# Automatic-Garden-Waterer.net
KiCad netlist of a schematic drawn in EAGLE
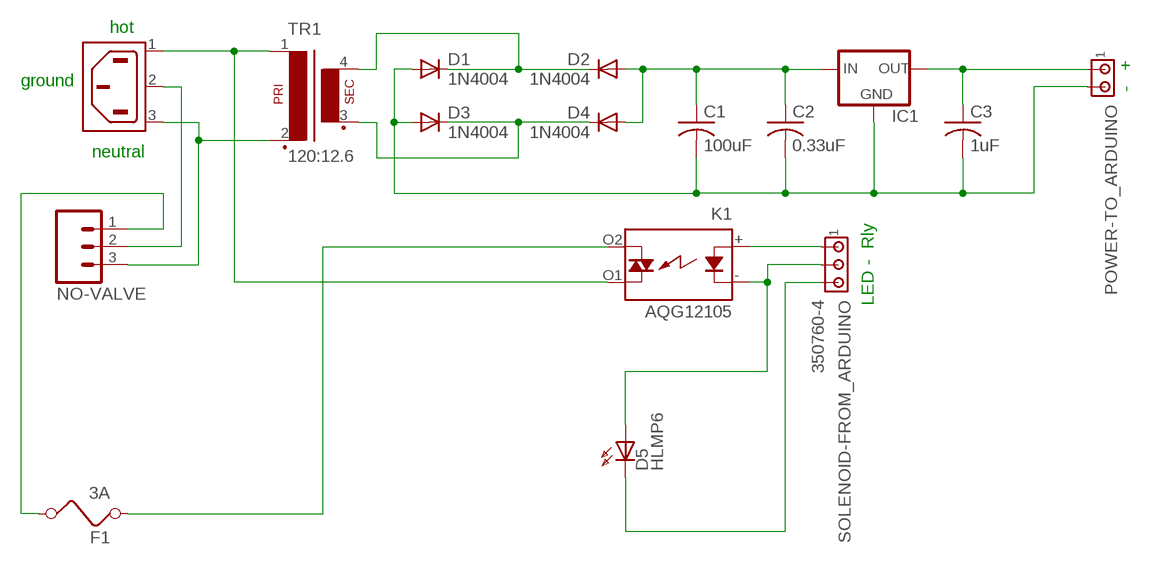
[diagram p0: schematic, sheet 1]

(export (version "E")
  (design (tool "Eeschema 10.0.6"))
  (components
    (comp (ref "C1")
      (value "100uF")
      (footprint "eagle-import:C075-032X103")
      (libsource (lib "eagle-import") (part "C-US075-032X103"))
    )
    (comp (ref "C2")
      (value "0.33uF")
      (footprint "eagle-import:C075-032X103")
      (libsource (lib "eagle-import") (part "C-US075-032X103"))
    )
    (comp (ref "C3")
      (value "1uF")
      (footprint "eagle-import:C075-032X103")
      (libsource (lib "eagle-import") (part "C-US075-032X103"))
    )
    (comp (ref "D1")
      (value "1N4004")
      (footprint "eagle-import:DO41-10")
      (libsource (lib "eagle-import") (part "1N4004"))
    )
    (comp (ref "D2")
      (value "1N4004")
      (footprint "eagle-import:DO41-10")
      (libsource (lib "eagle-import") (part "1N4004"))
    )
    (comp (ref "D3")
      (value "1N4004")
      (footprint "eagle-import:DO41-10")
      (libsource (lib "eagle-import") (part "1N4004"))
    )
    (comp (ref "D4")
      (value "1N4004")
      (footprint "eagle-import:DO41-10")
      (libsource (lib "eagle-import") (part "1N4004"))
    )
    (comp (ref "D5")
      (value "HLMP6")
      (footprint "eagle-import:HLMP6")
      (fields (field (name "MF") "AGILENT TECHNOLOGIES") (field (name "MPN") "HLMP-6500"))
      (libsource (lib "eagle-import") (part "HLMP6"))
    )
    (comp (ref "F1")
      (value "3A")
      (footprint "eagle-import:FUSE")
      (libsource (lib "eagle-import") (part "FUSE"))
    )
    (comp (ref "IC1")
      (value "V_REG_78XXSIDE")
      (footprint "eagle-import:78XXL")
      (libsource (lib "eagle-import") (part "V_REG_78XXSIDE"))
    )
    (comp (ref "K1")
      (value "AQG12105")
      (footprint "eagle-import:AQG")
      (fields (field (name "MF") "AROMAT/ MATSUSHITA"))
      (libsource (lib "eagle-import") (part "AQG12105"))
    )
    (comp (ref "NO-VALVE")
      (value "M03PTH")
      (footprint "eagle-import:1X03")
      (libsource (lib "eagle-import") (part "M03PTH"))
    )
    (comp (ref "POWER-TO_ARDUINO")
      (value "MTA02-100")
      (footprint "eagle-import:10X02MTA")
      (libsource (lib "eagle-import") (part "MTA02-100"))
    )
    (comp (ref "SOLENOID-FROM_ARDUINO")
      (value "350760-4")
      (footprint "eagle-import:350760-4")
      (libsource (lib "eagle-import") (part "350760-4"))
    )
    (comp (ref "TR1")
      (value "120:12.6")
      (footprint "eagle-import:VP31")
      (libsource (lib "eagle-import") (part "VP31"))
    )
    (comp (ref "X1")
      (value "6ESRM-P")
      (footprint "eagle-import:6ESRM-P")
      (fields (field (name "MF") "TYCO ELECTRONICS"))
      (libsource (lib "eagle-import") (part "6ESRM-P"))
    )
  )
  (nets
    (net (code "1") (name "Net-(C1-Pad1)") (class "Default")
      (node (ref "C1") (pin "1") (pinfunction "1_1") (pintype "passive"))
      (node (ref "C2") (pin "1") (pinfunction "1_1") (pintype "passive"))
      (node (ref "D2") (pin "A") (pinfunction "A_A") (pintype "passive"))
      (node (ref "D4") (pin "A") (pinfunction "A_A") (pintype "passive"))
      (node (ref "IC1") (pin "IN") (pinfunction "IN_IN") (pintype "input"))
    )
    (net (code "2") (name "Net-(C1-Pad2)") (class "Default")
      (node (ref "C1") (pin "2") (pinfunction "2_2") (pintype "passive"))
      (node (ref "C2") (pin "2") (pinfunction "2_2") (pintype "passive"))
      (node (ref "C3") (pin "2") (pinfunction "2_2") (pintype "passive"))
      (node (ref "D1") (pin "A") (pinfunction "A_A") (pintype "passive"))
      (node (ref "D3") (pin "A") (pinfunction "A_A") (pintype "passive"))
      (node (ref "IC1") (pin "GND") (pinfunction "GND_GND") (pintype "input"))
      (node (ref "POWER-TO_ARDUINO") (pin "2") (pinfunction "2_2") (pintype "passive"))
    )
    (net (code "3") (name "Net-(C3-Pad1)") (class "Default")
      (node (ref "C3") (pin "1") (pinfunction "1_1") (pintype "passive"))
      (node (ref "IC1") (pin "OUT") (pinfunction "OUT_OUT") (pintype "output"))
      (node (ref "POWER-TO_ARDUINO") (pin "1") (pinfunction "1_1") (pintype "passive"))
    )
    (net (code "4") (name "Net-(D5-PadK)") (class "Default")
      (node (ref "D5") (pin "K") (pinfunction "K_K") (pintype "passive"))
      (node (ref "SOLENOID-FROM_ARDUINO") (pin "3") (pinfunction "3_3") (pintype "passive"))
    )
    (net (code "5") (name "Net-(F1-Pad2)") (class "Default")
      (node (ref "F1") (pin "2") (pinfunction "2_2") (pintype "passive"))
      (node (ref "NO-VALVE") (pin "1") (pinfunction "1_1") (pintype "passive"))
    )
    (net (code "6") (name "Net-(K1-A)") (class "Default")
      (node (ref "K1") (pin "+") (pinfunction "A_+") (pintype "passive"))
      (node (ref "SOLENOID-FROM_ARDUINO") (pin "1") (pinfunction "1_1") (pintype "passive"))
    )
    (net (code "7") (name "Net-(K1-DS1)") (class "Default")
      (node (ref "F1") (pin "1") (pinfunction "1_1") (pintype "passive"))
      (node (ref "K1") (pin "O2") (pinfunction "DS1_O2") (pintype "passive"))
    )
    (net (code "8") (name "Net-(K1-DS2)") (class "Default")
      (node (ref "K1") (pin "O1") (pinfunction "DS2_O1") (pintype "passive"))
      (node (ref "TR1") (pin "1") (pinfunction "P1_1") (pintype "passive"))
      (node (ref "X1") (pin "1") (pinfunction "AC1_1") (pintype "passive"))
    )
    (net (code "9") (name "Net-(K1-K)") (class "Default")
      (node (ref "D5") (pin "A") (pinfunction "A_A") (pintype "passive"))
      (node (ref "K1") (pin "-") (pinfunction "K_-") (pintype "passive"))
      (node (ref "SOLENOID-FROM_ARDUINO") (pin "2") (pinfunction "2_2") (pintype "passive"))
    )
    (net (code "10") (name "Net-(TR1-P2)") (class "Default")
      (node (ref "NO-VALVE") (pin "3") (pinfunction "3_3") (pintype "passive"))
      (node (ref "TR1") (pin "2") (pinfunction "P2_2") (pintype "passive"))
      (node (ref "X1") (pin "3") (pinfunction "AC2_3") (pintype "passive"))
    )
    (net (code "11") (name "Net-(TR1-S3)") (class "Default")
      (node (ref "D3") (pin "C") (pinfunction "C_C") (pintype "passive"))
      (node (ref "D4") (pin "C") (pinfunction "C_C") (pintype "passive"))
      (node (ref "TR1") (pin "3") (pinfunction "S3_3") (pintype "passive"))
    )
    (net (code "12") (name "Net-(TR1-S4)") (class "Default")
      (node (ref "D1") (pin "C") (pinfunction "C_C") (pintype "passive"))
      (node (ref "D2") (pin "C") (pinfunction "C_C") (pintype "passive"))
      (node (ref "TR1") (pin "4") (pinfunction "S4_4") (pintype "passive"))
    )
    (net (code "13") (name "Net-(X1-SH)") (class "Default")
      (node (ref "NO-VALVE") (pin "2") (pinfunction "2_2") (pintype "passive"))
      (node (ref "X1") (pin "2") (pinfunction "SH_2") (pintype "passive"))
    )
  )
)
